# Input_Fuses.net
KiCad netlist of a schematic drawn in Altium Designer
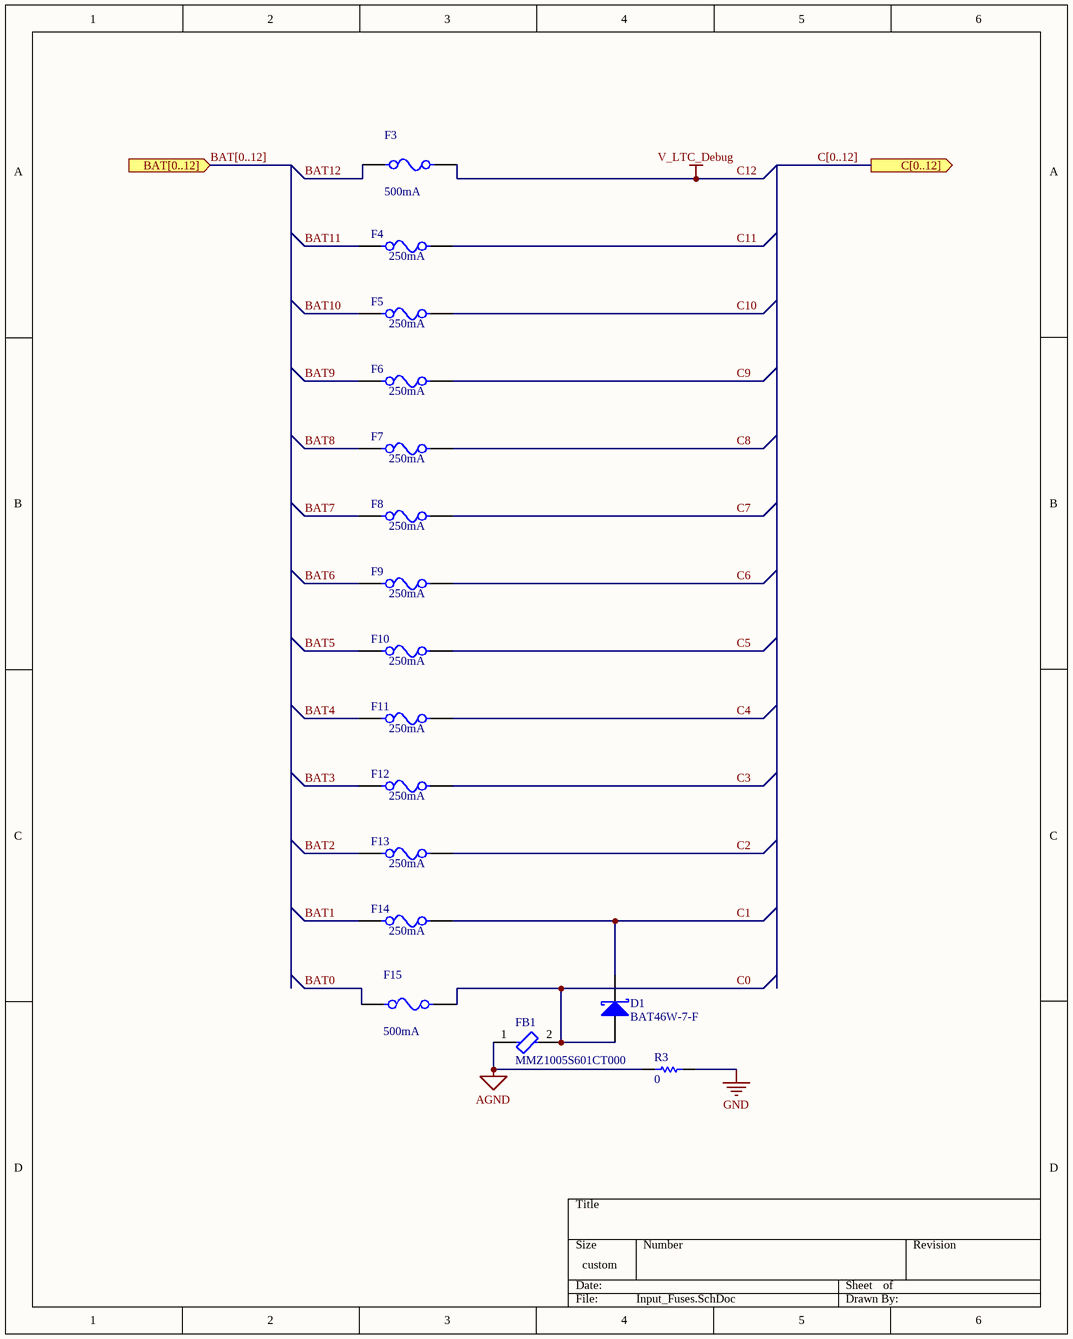
[diagram p0: Input_Fuses.SchDoc]

(export (version "E")
  (design (tool "Eeschema 10.0.6"))
  (components
    (comp (ref "D1")
      (value "BAT46W-7-F")
      (footprint "DIOD-SOD-123-2_V")
      (description "Surface Mount Schottky Barrier Diode, 100 V, -55 to 125 degC, 2-Pin SOD123, RoHS, Tape and Reel")
      (fields (field (name "MANUFACTURER") "Diodes Inc"))
      (libsource (lib "Altium Content Vault") (part "DIOD-DSKY-A1K2-2"))
    )
    (comp (ref "F3")
      (value "500mA")
      (footprint "Fuse_500_mA")
      (description "0679H0500-01, Sicherungen zur Aufbaumontage 500mA 350 VAC 72 VCD")
      (libsource (lib "LV-BMS") (part "Fuse_500mA"))
    )
    (comp (ref "F4")
      (value "250mA")
      (footprint "RESC0603(1608)_N")
      (description "Fuse, Fast Blow 250mA, 63VDC")
      (fields (field (name "MANUFACTURER") "Bel Fuse"))
      (libsource (lib "LV-BMS") (part "Bel Fuse C2Q250"))
    )
    (comp (ref "F5")
      (value "250mA")
      (footprint "RESC0603(1608)_N")
      (description "Fuse, Fast Blow 250mA, 63VDC")
      (fields (field (name "MANUFACTURER") "Bel Fuse"))
      (libsource (lib "LV-BMS") (part "Bel Fuse C2Q250"))
    )
    (comp (ref "F6")
      (value "250mA")
      (footprint "RESC0603(1608)_N")
      (description "Fuse, Fast Blow 250mA, 63VDC")
      (fields (field (name "MANUFACTURER") "Bel Fuse"))
      (libsource (lib "LV-BMS") (part "Bel Fuse C2Q250"))
    )
    (comp (ref "F7")
      (value "250mA")
      (footprint "RESC0603(1608)_N")
      (description "Fuse, Fast Blow 250mA, 63VDC")
      (fields (field (name "MANUFACTURER") "Bel Fuse"))
      (libsource (lib "LV-BMS") (part "Bel Fuse C2Q250"))
    )
    (comp (ref "F8")
      (value "250mA")
      (footprint "RESC0603(1608)_N")
      (description "Fuse, Fast Blow 250mA, 63VDC")
      (fields (field (name "MANUFACTURER") "Bel Fuse"))
      (libsource (lib "LV-BMS") (part "Bel Fuse C2Q250"))
    )
    (comp (ref "F9")
      (value "250mA")
      (footprint "RESC0603(1608)_N")
      (description "Fuse, Fast Blow 250mA, 63VDC")
      (fields (field (name "MANUFACTURER") "Bel Fuse"))
      (libsource (lib "LV-BMS") (part "Bel Fuse C2Q250"))
    )
    (comp (ref "F10")
      (value "250mA")
      (footprint "RESC0603(1608)_N")
      (description "Fuse, Fast Blow 250mA, 63VDC")
      (fields (field (name "MANUFACTURER") "Bel Fuse"))
      (libsource (lib "LV-BMS") (part "Bel Fuse C2Q250"))
    )
    (comp (ref "F11")
      (value "250mA")
      (footprint "RESC0603(1608)_N")
      (description "Fuse, Fast Blow 250mA, 63VDC")
      (fields (field (name "MANUFACTURER") "Bel Fuse"))
      (libsource (lib "LV-BMS") (part "Bel Fuse C2Q250"))
    )
    (comp (ref "F12")
      (value "250mA")
      (footprint "RESC0603(1608)_N")
      (description "Fuse, Fast Blow 250mA, 63VDC")
      (fields (field (name "MANUFACTURER") "Bel Fuse"))
      (libsource (lib "LV-BMS") (part "Bel Fuse C2Q250"))
    )
    (comp (ref "F13")
      (value "250mA")
      (footprint "RESC0603(1608)_N")
      (description "Fuse, Fast Blow 250mA, 63VDC")
      (fields (field (name "MANUFACTURER") "Bel Fuse"))
      (libsource (lib "LV-BMS") (part "Bel Fuse C2Q250"))
    )
    (comp (ref "F14")
      (value "250mA")
      (footprint "RESC0603(1608)_N")
      (description "Fuse, Fast Blow 250mA, 63VDC")
      (fields (field (name "MANUFACTURER") "Bel Fuse"))
      (libsource (lib "LV-BMS") (part "Bel Fuse C2Q250"))
    )
    (comp (ref "F15")
      (value "500mA")
      (footprint "Fuse_500_mA")
      (description "0679H0500-01, Sicherungen zur Aufbaumontage 500mA 350 VAC 72 VCD")
      (libsource (lib "LV-BMS") (part "Fuse_500mA"))
    )
    (comp (ref "FB1")
      (value "MMZ1005S601CT000")
      (footprint "FP-MMZ1005-MFG")
      (description " Signal Line Ferrite Bead 600Ω @ 100MHz 300mA DCR 520mΩ SMD 0402")
      (fields (field (name "TOLERANCE") "25%"))
      (libsource (lib "Altium Content Vault") (part "5f30dd21d616792df468990f7003faa"))
    )
    (comp (ref "R3")
      (value "0")
      (footprint "RESC0603(1608)_N")
      (description "Chipwiderstand, SMD, Baureihe MC, 1%")
      (fields (field (name "MANUFACTURER") "Multicomp") (field (name "POWER") "100mW"))
      (libsource (lib "Res&Caps") (part "Res 0R"))
    )
  )
  (nets
    (net (code "1") (name "/BAT0") (class "Default")
      (node (ref "F15") (pin "2") (pinfunction "2_2") (pintype "passive"))
    )
    (net (code "2") (name "/BAT1") (class "Default")
      (node (ref "F14") (pin "1") (pinfunction "1_1") (pintype "passive"))
    )
    (net (code "3") (name "/BAT2") (class "Default")
      (node (ref "F13") (pin "1") (pinfunction "1_1") (pintype "passive"))
    )
    (net (code "4") (name "/BAT3") (class "Default")
      (node (ref "F12") (pin "1") (pinfunction "1_1") (pintype "passive"))
    )
    (net (code "5") (name "/BAT4") (class "Default")
      (node (ref "F11") (pin "1") (pinfunction "1_1") (pintype "passive"))
    )
    (net (code "6") (name "/BAT5") (class "Default")
      (node (ref "F10") (pin "1") (pinfunction "1_1") (pintype "passive"))
    )
    (net (code "7") (name "/BAT6") (class "Default")
      (node (ref "F9") (pin "1") (pinfunction "1_1") (pintype "passive"))
    )
    (net (code "8") (name "/BAT7") (class "Default")
      (node (ref "F8") (pin "1") (pinfunction "1_1") (pintype "passive"))
    )
    (net (code "9") (name "/BAT8") (class "Default")
      (node (ref "F7") (pin "1") (pinfunction "1_1") (pintype "passive"))
    )
    (net (code "10") (name "/BAT9") (class "Default")
      (node (ref "F6") (pin "1") (pinfunction "1_1") (pintype "passive"))
    )
    (net (code "11") (name "/BAT10") (class "Default")
      (node (ref "F5") (pin "1") (pinfunction "1_1") (pintype "passive"))
    )
    (net (code "12") (name "/BAT11") (class "Default")
      (node (ref "F4") (pin "1") (pinfunction "1_1") (pintype "passive"))
    )
    (net (code "13") (name "/BAT12") (class "Default")
      (node (ref "F3") (pin "2") (pinfunction "2_2") (pintype "passive"))
    )
    (net (code "15") (name "/C0") (class "Default")
      (node (ref "D1") (pin "1") (pinfunction "A_1") (pintype "passive"))
      (node (ref "F15") (pin "1") (pinfunction "1_1") (pintype "passive"))
      (node (ref "FB1") (pin "2") (pinfunction "2_2") (pintype "passive"))
    )
    (net (code "16") (name "/C1") (class "Default")
      (node (ref "D1") (pin "2") (pinfunction "K_2") (pintype "passive"))
      (node (ref "F14") (pin "2") (pinfunction "2_2") (pintype "passive"))
    )
    (net (code "17") (name "/C2") (class "Default")
      (node (ref "F13") (pin "2") (pinfunction "2_2") (pintype "passive"))
    )
    (net (code "18") (name "/C3") (class "Default")
      (node (ref "F12") (pin "2") (pinfunction "2_2") (pintype "passive"))
    )
    (net (code "19") (name "/C4") (class "Default")
      (node (ref "F11") (pin "2") (pinfunction "2_2") (pintype "passive"))
    )
    (net (code "20") (name "/C5") (class "Default")
      (node (ref "F10") (pin "2") (pinfunction "2_2") (pintype "passive"))
    )
    (net (code "21") (name "/C6") (class "Default")
      (node (ref "F9") (pin "2") (pinfunction "2_2") (pintype "passive"))
    )
    (net (code "22") (name "/C7") (class "Default")
      (node (ref "F8") (pin "2") (pinfunction "2_2") (pintype "passive"))
    )
    (net (code "23") (name "/C8") (class "Default")
      (node (ref "F7") (pin "2") (pinfunction "2_2") (pintype "passive"))
    )
    (net (code "24") (name "/C9") (class "Default")
      (node (ref "F6") (pin "2") (pinfunction "2_2") (pintype "passive"))
    )
    (net (code "25") (name "/C10") (class "Default")
      (node (ref "F5") (pin "2") (pinfunction "2_2") (pintype "passive"))
    )
    (net (code "26") (name "/C11") (class "Default")
      (node (ref "F4") (pin "2") (pinfunction "2_2") (pintype "passive"))
    )
    (net (code "28") (name "AGND") (class "Default")
      (node (ref "FB1") (pin "1") (pinfunction "1_1") (pintype "passive"))
      (node (ref "R3") (pin "2") (pinfunction "2_2") (pintype "passive"))
    )
    (net (code "29") (name "GND") (class "Default")
      (node (ref "R3") (pin "1") (pinfunction "1_1") (pintype "passive"))
    )
    (net (code "30") (name "V_LTC_Debug") (class "Default")
      (node (ref "F3") (pin "1") (pinfunction "1_1") (pintype "passive"))
    )
  )
)
